# Autopilot.net
KiCad netlist of a schematic drawn in EAGLE
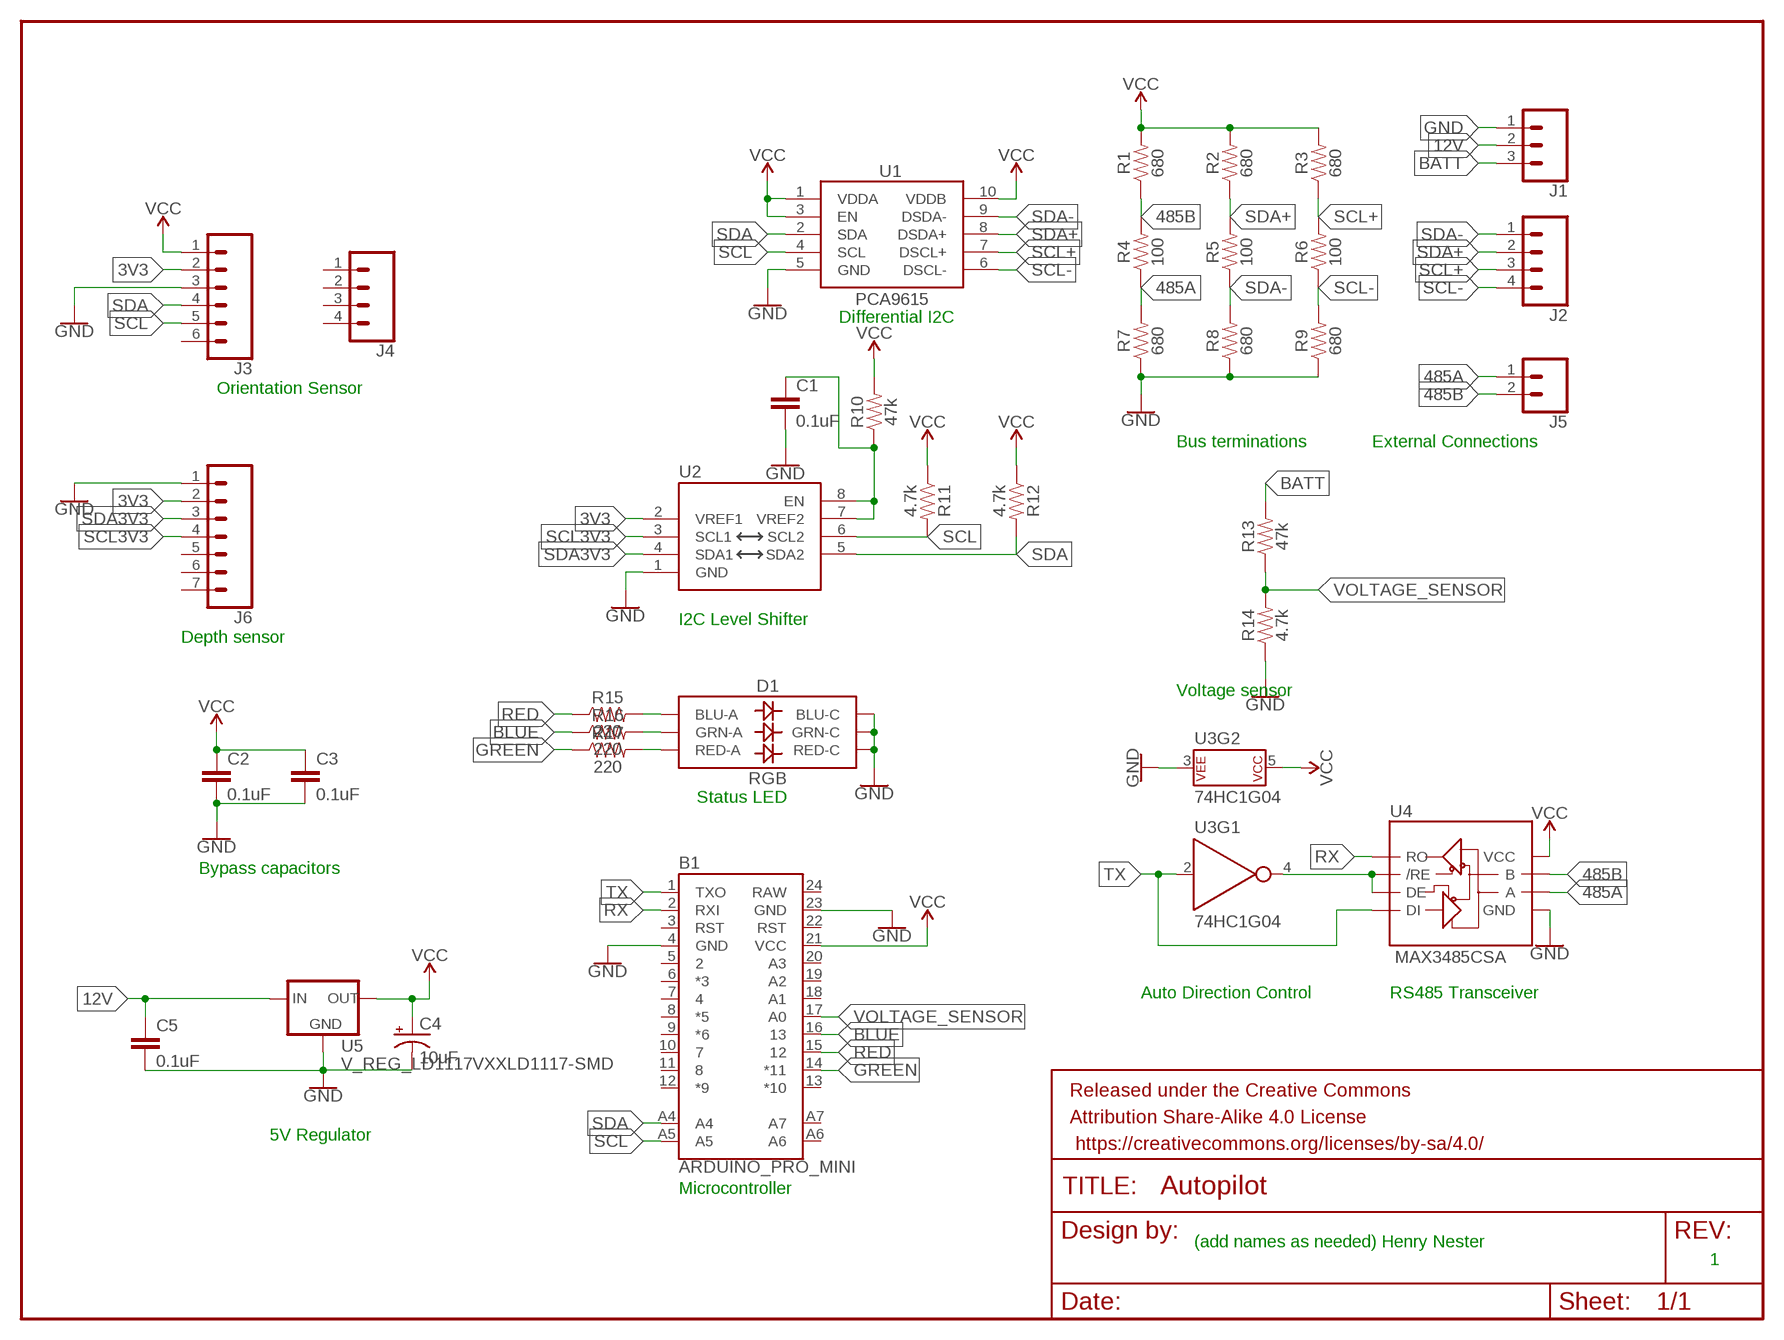
[diagram p0: schematic, sheet 1]

(export (version "E")
  (design (tool "Eeschema 10.0.6"))
  (components
    (comp (ref "B1")
      (value "ARDUINO_PRO_MINI")
      (footprint "eagle-import:ARDUINO_PRO_MINI")
      (libsource (lib "eagle-import") (part "ARDUINO_PRO_MINI"))
    )
    (comp (ref "C1")
      (value "0.1uF")
      (footprint "eagle-import:0603")
      (libsource (lib "eagle-import") (part "0.1UF-0603-25V-(+80/-20%)"))
    )
    (comp (ref "C2")
      (value "0.1uF")
      (footprint "eagle-import:0603")
      (libsource (lib "eagle-import") (part "0.1UF-0603-25V-(+80/-20%)"))
    )
    (comp (ref "C3")
      (value "0.1uF")
      (footprint "eagle-import:0603")
      (libsource (lib "eagle-import") (part "0.1UF-0603-25V-(+80/-20%)"))
    )
    (comp (ref "C4")
      (value "10uF")
      (footprint "eagle-import:CPOL-RADIAL-2.5MM-5MM")
      (libsource (lib "eagle-import") (part "10UF-POLAR-RADIAL-2.5MM-25V-20%"))
    )
    (comp (ref "C5")
      (value "0.1uF")
      (footprint "eagle-import:0603")
      (libsource (lib "eagle-import") (part "0.1UF-0603-25V-(+80/-20%)"))
    )
    (comp (ref "D1")
      (value "RGB")
      (footprint "eagle-import:PLCC-6-LED")
      (libsource (lib "eagle-import") (part "LED-RGBPLCC-6"))
    )
    (comp (ref "FRAME1")
      (value "FRAME-LETTERNO_PACKAGE")
      (footprint "eagle-import:DUMMY")
      (fields (field (name "DESIGNER") "Nobody"))
      (libsource (lib "eagle-import") (part "FRAME-LETTERNO_PACKAGE"))
    )
    (comp (ref "J1")
      (value "CONN_03LONGPADS")
      (footprint "eagle-import:1X03_LONGPADS")
      (libsource (lib "eagle-import") (part "CONN_03LONGPADS"))
    )
    (comp (ref "J2")
      (value "CONN_04")
      (footprint "eagle-import:1X04")
      (libsource (lib "eagle-import") (part "CONN_04"))
    )
    (comp (ref "J3")
      (value "CONN_06NO_SILK_FEMALE_PTH")
      (footprint "eagle-import:1X06_NO_SILK")
      (libsource (lib "eagle-import") (part "CONN_06NO_SILK_FEMALE_PTH"))
    )
    (comp (ref "J4")
      (value "CONN_041X04_NO_SILK")
      (footprint "eagle-import:1X04_NO_SILK")
      (libsource (lib "eagle-import") (part "CONN_041X04_NO_SILK"))
    )
    (comp (ref "J5")
      (value "CONN_02")
      (footprint "eagle-import:1X02")
      (libsource (lib "eagle-import") (part "CONN_02"))
    )
    (comp (ref "J6")
      (value "CONN_07NO_SILK")
      (footprint "eagle-import:1X07_NO_SILK")
      (libsource (lib "eagle-import") (part "CONN_07NO_SILK"))
    )
    (comp (ref "R1")
      (value "680")
      (footprint "eagle-import:0603")
      (libsource (lib "eagle-import") (part "680OHM-0603-1/10W-5%"))
    )
    (comp (ref "R2")
      (value "680")
      (footprint "eagle-import:0603")
      (libsource (lib "eagle-import") (part "680OHM-0603-1/10W-5%"))
    )
    (comp (ref "R3")
      (value "680")
      (footprint "eagle-import:0603")
      (libsource (lib "eagle-import") (part "680OHM-0603-1/10W-5%"))
    )
    (comp (ref "R4")
      (value "100")
      (footprint "eagle-import:0603")
      (libsource (lib "eagle-import") (part "100OHM-0603-1/4W-5%"))
    )
    (comp (ref "R5")
      (value "100")
      (footprint "eagle-import:0603")
      (libsource (lib "eagle-import") (part "100OHM-0603-1/4W-5%"))
    )
    (comp (ref "R6")
      (value "100")
      (footprint "eagle-import:0603")
      (libsource (lib "eagle-import") (part "100OHM-0603-1/4W-5%"))
    )
    (comp (ref "R7")
      (value "680")
      (footprint "eagle-import:0603")
      (libsource (lib "eagle-import") (part "680OHM-0603-1/10W-5%"))
    )
    (comp (ref "R8")
      (value "680")
      (footprint "eagle-import:0603")
      (libsource (lib "eagle-import") (part "680OHM-0603-1/10W-5%"))
    )
    (comp (ref "R9")
      (value "680")
      (footprint "eagle-import:0603")
      (libsource (lib "eagle-import") (part "680OHM-0603-1/10W-5%"))
    )
    (comp (ref "R10")
      (value "47k")
      (footprint "eagle-import:0603")
      (libsource (lib "eagle-import") (part "100KOHM-0603-1/10W-1%"))
    )
    (comp (ref "R11")
      (value "4.7k")
      (footprint "eagle-import:0603")
      (libsource (lib "eagle-import") (part "4.7KOHM-0603-1/10W-1%"))
    )
    (comp (ref "R12")
      (value "4.7k")
      (footprint "eagle-import:0603")
      (libsource (lib "eagle-import") (part "4.7KOHM-0603-1/10W-1%"))
    )
    (comp (ref "R13")
      (value "47k")
      (footprint "eagle-import:0603")
      (libsource (lib "eagle-import") (part "100KOHM-0603-1/10W-1%"))
    )
    (comp (ref "R14")
      (value "4.7k")
      (footprint "eagle-import:0603")
      (libsource (lib "eagle-import") (part "4.7KOHM-0603-1/10W-1%"))
    )
    (comp (ref "R15")
      (value "220")
      (footprint "eagle-import:0603")
      (libsource (lib "eagle-import") (part "220OHM-0603-1/10W-1%"))
    )
    (comp (ref "R16")
      (value "220")
      (footprint "eagle-import:0603")
      (libsource (lib "eagle-import") (part "220OHM-0603-1/10W-1%"))
    )
    (comp (ref "R17")
      (value "220")
      (footprint "eagle-import:0603")
      (libsource (lib "eagle-import") (part "220OHM-0603-1/10W-1%"))
    )
    (comp (ref "U1")
      (value "PCA9615")
      (footprint "eagle-import:TSSOP10")
      (libsource (lib "eagle-import") (part "PCA9615"))
    )
    (comp (ref "U2")
      (value "PCA9306MSOP-8")
      (footprint "eagle-import:MSOP8")
      (libsource (lib "eagle-import") (part "PCA9306MSOP-8"))
    )
    (comp (ref "U3")
      (value "74HC1G04")
      (footprint "eagle-import:SOT353")
      (libsource (lib "eagle-import") (part "741G04HC"))
    )
    (comp (ref "U4")
      (value "MAX3485CSA")
      (footprint "eagle-import:SO08")
      (libsource (lib "eagle-import") (part "RS485SOIC"))
    )
    (comp (ref "U5")
      (value "V_REG_LD1117VXXLD1117-SMD")
      (footprint "eagle-import:SOT223")
      (libsource (lib "eagle-import") (part "V_REG_LD1117VXXLD1117-SMD"))
    )
  )
  (nets
    (net (code "1") (name "/RAW") (class "Default")
      (node (ref "B1") (pin "24") (pinfunction "RAW_24") (pintype "power_in"))
    )
    (net (code "2") (name "3V3") (class "Default")
      (node (ref "J3") (pin "2") (pinfunction "2_2") (pintype "passive"))
      (node (ref "J6") (pin "2") (pinfunction "2_2") (pintype "passive"))
      (node (ref "U2") (pin "2") (pinfunction "VREF1_2") (pintype "bidirectional"))
    )
    (net (code "3") (name "12V") (class "Default")
      (node (ref "C5") (pin "1") (pinfunction "1_1") (pintype "passive"))
      (node (ref "J1") (pin "2") (pinfunction "2_2") (pintype "passive"))
      (node (ref "U5") (pin "3") (pinfunction "IN_3") (pintype "input"))
    )
    (net (code "4") (name "485A") (class "Default")
      (node (ref "J5") (pin "1") (pinfunction "1_1") (pintype "passive"))
      (node (ref "R4") (pin "1") (pinfunction "1_1") (pintype "passive"))
      (node (ref "R7") (pin "2") (pinfunction "2_2") (pintype "passive"))
      (node (ref "U4") (pin "6") (pinfunction "A_6") (pintype "bidirectional"))
    )
    (net (code "5") (name "485B") (class "Default")
      (node (ref "J5") (pin "2") (pinfunction "2_2") (pintype "passive"))
      (node (ref "R1") (pin "1") (pinfunction "1_1") (pintype "passive"))
      (node (ref "R4") (pin "2") (pinfunction "2_2") (pintype "passive"))
      (node (ref "U4") (pin "7") (pinfunction "B_7") (pintype "bidirectional"))
    )
    (net (code "6") (name "BATT") (class "Default")
      (node (ref "J1") (pin "3") (pinfunction "3_3") (pintype "passive"))
      (node (ref "R13") (pin "2") (pinfunction "2_2") (pintype "passive"))
    )
    (net (code "7") (name "BLUE") (class "Default")
      (node (ref "B1") (pin "16") (pinfunction "13_16") (pintype "bidirectional"))
      (node (ref "R16") (pin "1") (pinfunction "1_1") (pintype "passive"))
    )
    (net (code "8") (name "GND") (class "Default")
      (node (ref "B1") (pin "23") (pinfunction "GND_23") (pintype "power_in"))
      (node (ref "B1") (pin "4") (pinfunction "GND_4") (pintype "power_in"))
      (node (ref "C1") (pin "2") (pinfunction "2_2") (pintype "passive"))
      (node (ref "C2") (pin "2") (pinfunction "2_2") (pintype "passive"))
      (node (ref "C3") (pin "2") (pinfunction "2_2") (pintype "passive"))
      (node (ref "C4") (pin "2") (pinfunction "-_2") (pintype "passive"))
      (node (ref "C5") (pin "2") (pinfunction "2_2") (pintype "passive"))
      (node (ref "D1") (pin "CB") (pinfunction "BLU-C_CB") (pintype "bidirectional"))
      (node (ref "D1") (pin "CG") (pinfunction "GRN-C_CG") (pintype "bidirectional"))
      (node (ref "D1") (pin "CR") (pinfunction "RED-C_CR") (pintype "bidirectional"))
      (node (ref "J1") (pin "1") (pinfunction "1_1") (pintype "passive"))
      (node (ref "J3") (pin "3") (pinfunction "3_3") (pintype "passive"))
      (node (ref "J6") (pin "1") (pinfunction "1_1") (pintype "passive"))
      (node (ref "R14") (pin "1") (pinfunction "1_1") (pintype "passive"))
      (node (ref "R7") (pin "1") (pinfunction "1_1") (pintype "passive"))
      (node (ref "R8") (pin "1") (pinfunction "1_1") (pintype "passive"))
      (node (ref "R9") (pin "1") (pinfunction "1_1") (pintype "passive"))
      (node (ref "U1") (pin "5") (pinfunction "GND_5") (pintype "bidirectional"))
      (node (ref "U2") (pin "1") (pinfunction "GND_1") (pintype "bidirectional"))
      (node (ref "U3") (pin "3") (pinfunction "P$V-_3") (pintype "bidirectional"))
      (node (ref "U4") (pin "5") (pinfunction "GND_5") (pintype "bidirectional"))
      (node (ref "U5") (pin "1") (pinfunction "GND_1") (pintype "input"))
    )
    (net (code "9") (name "GREEN") (class "Default")
      (node (ref "B1") (pin "14") (pinfunction "*11_14") (pintype "bidirectional"))
      (node (ref "R17") (pin "1") (pinfunction "1_1") (pintype "passive"))
    )
    (net (code "10") (name "Net-(D1-BLU-A)") (class "Default")
      (node (ref "D1") (pin "AB") (pinfunction "BLU-A_AB") (pintype "bidirectional"))
      (node (ref "R15") (pin "2") (pinfunction "2_2") (pintype "passive"))
    )
    (net (code "11") (name "Net-(D1-GRN-A)") (class "Default")
      (node (ref "D1") (pin "AG") (pinfunction "GRN-A_AG") (pintype "bidirectional"))
      (node (ref "R16") (pin "2") (pinfunction "2_2") (pintype "passive"))
    )
    (net (code "12") (name "Net-(D1-RED-A)") (class "Default")
      (node (ref "D1") (pin "AR") (pinfunction "RED-A_AR") (pintype "bidirectional"))
      (node (ref "R17") (pin "2") (pinfunction "2_2") (pintype "passive"))
    )
    (net (code "13") (name "Net-(U2-EN)") (class "Default")
      (node (ref "C1") (pin "1") (pinfunction "1_1") (pintype "passive"))
      (node (ref "R10") (pin "1") (pinfunction "1_1") (pintype "passive"))
      (node (ref "U2") (pin "7") (pinfunction "VREF2_7") (pintype "bidirectional"))
      (node (ref "U2") (pin "8") (pinfunction "EN_8") (pintype "bidirectional"))
    )
    (net (code "14") (name "Net-(U3A-Y)") (class "Default")
      (node (ref "U3") (pin "4") (pinfunction "Y_4") (pintype "bidirectional"))
      (node (ref "U4") (pin "2") (pinfunction "/RE_2") (pintype "bidirectional"))
      (node (ref "U4") (pin "3") (pinfunction "DE_3") (pintype "bidirectional"))
    )
    (net (code "15") (name "RED") (class "Default")
      (node (ref "B1") (pin "15") (pinfunction "12_15") (pintype "bidirectional"))
      (node (ref "R15") (pin "1") (pinfunction "1_1") (pintype "passive"))
    )
    (net (code "16") (name "RX") (class "Default")
      (node (ref "B1") (pin "2") (pinfunction "RXI_2") (pintype "bidirectional"))
      (node (ref "U4") (pin "1") (pinfunction "RO_1") (pintype "bidirectional"))
    )
    (net (code "17") (name "SCL") (class "Default")
      (node (ref "B1") (pin "A5") (pinfunction "A5_A5") (pintype "bidirectional"))
      (node (ref "J3") (pin "5") (pinfunction "5_5") (pintype "passive"))
      (node (ref "R11") (pin "2") (pinfunction "2_2") (pintype "passive"))
      (node (ref "U1") (pin "4") (pinfunction "SCL_4") (pintype "bidirectional"))
      (node (ref "U2") (pin "6") (pinfunction "SCL2_6") (pintype "bidirectional"))
    )
    (net (code "18") (name "SCL+") (class "Default")
      (node (ref "J2") (pin "3") (pinfunction "3_3") (pintype "passive"))
      (node (ref "R3") (pin "1") (pinfunction "1_1") (pintype "passive"))
      (node (ref "R6") (pin "2") (pinfunction "2_2") (pintype "passive"))
      (node (ref "U1") (pin "7") (pinfunction "DSCL+_7") (pintype "bidirectional"))
    )
    (net (code "19") (name "SCL-") (class "Default")
      (node (ref "J2") (pin "4") (pinfunction "4_4") (pintype "passive"))
      (node (ref "R6") (pin "1") (pinfunction "1_1") (pintype "passive"))
      (node (ref "R9") (pin "2") (pinfunction "2_2") (pintype "passive"))
      (node (ref "U1") (pin "6") (pinfunction "DSCL-_6") (pintype "bidirectional"))
    )
    (net (code "20") (name "SCL3V3") (class "Default")
      (node (ref "J6") (pin "4") (pinfunction "4_4") (pintype "passive"))
      (node (ref "U2") (pin "3") (pinfunction "SCL1_3") (pintype "bidirectional"))
    )
    (net (code "21") (name "SDA") (class "Default")
      (node (ref "B1") (pin "A4") (pinfunction "A4_A4") (pintype "bidirectional"))
      (node (ref "J3") (pin "4") (pinfunction "4_4") (pintype "passive"))
      (node (ref "R12") (pin "2") (pinfunction "2_2") (pintype "passive"))
      (node (ref "U1") (pin "2") (pinfunction "SDA_2") (pintype "bidirectional"))
      (node (ref "U2") (pin "5") (pinfunction "SDA2_5") (pintype "bidirectional"))
    )
    (net (code "22") (name "SDA+") (class "Default")
      (node (ref "J2") (pin "2") (pinfunction "2_2") (pintype "passive"))
      (node (ref "R2") (pin "1") (pinfunction "1_1") (pintype "passive"))
      (node (ref "R5") (pin "2") (pinfunction "2_2") (pintype "passive"))
      (node (ref "U1") (pin "8") (pinfunction "DSDA+_8") (pintype "bidirectional"))
    )
    (net (code "23") (name "SDA-") (class "Default")
      (node (ref "J2") (pin "1") (pinfunction "1_1") (pintype "passive"))
      (node (ref "R5") (pin "1") (pinfunction "1_1") (pintype "passive"))
      (node (ref "R8") (pin "2") (pinfunction "2_2") (pintype "passive"))
      (node (ref "U1") (pin "9") (pinfunction "DSDA-_9") (pintype "bidirectional"))
    )
    (net (code "24") (name "SDA3V3") (class "Default")
      (node (ref "J6") (pin "3") (pinfunction "3_3") (pintype "passive"))
      (node (ref "U2") (pin "4") (pinfunction "SDA1_4") (pintype "bidirectional"))
    )
    (net (code "25") (name "TX") (class "Default")
      (node (ref "B1") (pin "1") (pinfunction "TXO_1") (pintype "bidirectional"))
      (node (ref "U3") (pin "2") (pinfunction "A_2") (pintype "bidirectional"))
      (node (ref "U4") (pin "4") (pinfunction "DI_4") (pintype "bidirectional"))
    )
    (net (code "26") (name "VCC") (class "Default")
      (node (ref "B1") (pin "21") (pinfunction "VCC_21") (pintype "power_in"))
      (node (ref "C2") (pin "1") (pinfunction "1_1") (pintype "passive"))
      (node (ref "C3") (pin "1") (pinfunction "1_1") (pintype "passive"))
      (node (ref "C4") (pin "1") (pinfunction "+_1") (pintype "passive"))
      (node (ref "J3") (pin "1") (pinfunction "1_1") (pintype "passive"))
      (node (ref "R1") (pin "2") (pinfunction "2_2") (pintype "passive"))
      (node (ref "R10") (pin "2") (pinfunction "2_2") (pintype "passive"))
      (node (ref "R11") (pin "1") (pinfunction "1_1") (pintype "passive"))
      (node (ref "R12") (pin "1") (pinfunction "1_1") (pintype "passive"))
      (node (ref "R2") (pin "2") (pinfunction "2_2") (pintype "passive"))
      (node (ref "R3") (pin "2") (pinfunction "2_2") (pintype "passive"))
      (node (ref "U1") (pin "1") (pinfunction "VDDA_1") (pintype "bidirectional"))
      (node (ref "U1") (pin "10") (pinfunction "VDDB_10") (pintype "bidirectional"))
      (node (ref "U1") (pin "3") (pinfunction "EN_3") (pintype "bidirectional"))
      (node (ref "U3") (pin "5") (pinfunction "P$V+_5") (pintype "bidirectional"))
      (node (ref "U4") (pin "8") (pinfunction "VCC_8") (pintype "bidirectional"))
      (node (ref "U5") (pin "2") (pinfunction "OUT_2") (pintype "passive"))
    )
    (net (code "27") (name "VOLTAGE_SENSOR") (class "Default")
      (node (ref "B1") (pin "17") (pinfunction "A0_17") (pintype "bidirectional"))
      (node (ref "R13") (pin "1") (pinfunction "1_1") (pintype "passive"))
      (node (ref "R14") (pin "2") (pinfunction "2_2") (pintype "passive"))
    )
    (net (code "28") (name "unconnected-(B1-*3-Pad6)") (class "Default")
      (node (ref "B1") (pin "6") (pinfunction "*3_6") (pintype "bidirectional"))
    )
    (net (code "29") (name "unconnected-(B1-*5-Pad8)") (class "Default")
      (node (ref "B1") (pin "8") (pinfunction "*5_8") (pintype "bidirectional"))
    )
    (net (code "30") (name "unconnected-(B1-*6-Pad9)") (class "Default")
      (node (ref "B1") (pin "9") (pinfunction "*6_9") (pintype "bidirectional"))
    )
    (net (code "31") (name "unconnected-(B1-*9-Pad12)") (class "Default")
      (node (ref "B1") (pin "12") (pinfunction "*9_12") (pintype "bidirectional"))
    )
    (net (code "32") (name "unconnected-(B1-*10-Pad13)") (class "Default")
      (node (ref "B1") (pin "13") (pinfunction "*10_13") (pintype "bidirectional"))
    )
    (net (code "33") (name "unconnected-(B1-2-Pad5)") (class "Default")
      (node (ref "B1") (pin "5") (pinfunction "2_5") (pintype "bidirectional"))
    )
    (net (code "34") (name "unconnected-(B1-4-Pad7)") (class "Default")
      (node (ref "B1") (pin "7") (pinfunction "4_7") (pintype "bidirectional"))
    )
    (net (code "35") (name "unconnected-(B1-7-Pad10)") (class "Default")
      (node (ref "B1") (pin "10") (pinfunction "7_10") (pintype "bidirectional"))
    )
    (net (code "36") (name "unconnected-(B1-8-Pad11)") (class "Default")
      (node (ref "B1") (pin "11") (pinfunction "8_11") (pintype "bidirectional"))
    )
    (net (code "37") (name "unconnected-(B1-A1-Pad18)") (class "Default")
      (node (ref "B1") (pin "18") (pinfunction "A1_18") (pintype "bidirectional"))
    )
    (net (code "38") (name "unconnected-(B1-A2-Pad19)") (class "Default")
      (node (ref "B1") (pin "19") (pinfunction "A2_19") (pintype "bidirectional"))
    )
    (net (code "39") (name "unconnected-(B1-A3-Pad20)") (class "Default")
      (node (ref "B1") (pin "20") (pinfunction "A3_20") (pintype "bidirectional"))
    )
    (net (code "40") (name "unconnected-(B1-PadA6)") (class "Default")
      (node (ref "B1") (pin "A6") (pinfunction "A6_A6") (pintype "bidirectional"))
    )
    (net (code "41") (name "unconnected-(B1-PadA7)") (class "Default")
      (node (ref "B1") (pin "A7") (pinfunction "A7_A7") (pintype "bidirectional"))
    )
    (net (code "42") (name "unconnected-(B1-RST-Pad3)") (class "Default")
      (node (ref "B1") (pin "3") (pinfunction "RST_3") (pintype "bidirectional"))
    )
    (net (code "43") (name "unconnected-(B1-RST-Pad22)") (class "Default")
      (node (ref "B1") (pin "22") (pinfunction "RST_22") (pintype "bidirectional"))
    )
    (net (code "44") (name "unconnected-(J3-Pad6)") (class "Default")
      (node (ref "J3") (pin "6") (pinfunction "6_6") (pintype "passive"))
    )
    (net (code "45") (name "unconnected-(J4-Pad1)") (class "Default")
      (node (ref "J4") (pin "1") (pinfunction "1_1") (pintype "passive"))
    )
    (net (code "46") (name "unconnected-(J4-Pad2)") (class "Default")
      (node (ref "J4") (pin "2") (pinfunction "2_2") (pintype "passive"))
    )
    (net (code "47") (name "unconnected-(J4-Pad3)") (class "Default")
      (node (ref "J4") (pin "3") (pinfunction "3_3") (pintype "passive"))
    )
    (net (code "48") (name "unconnected-(J4-Pad4)") (class "Default")
      (node (ref "J4") (pin "4") (pinfunction "4_4") (pintype "passive"))
    )
    (net (code "49") (name "unconnected-(J6-Pad5)") (class "Default")
      (node (ref "J6") (pin "5") (pinfunction "5_5") (pintype "passive"))
    )
    (net (code "50") (name "unconnected-(J6-Pad6)") (class "Default")
      (node (ref "J6") (pin "6") (pinfunction "6_6") (pintype "passive"))
    )
    (net (code "51") (name "unconnected-(J6-Pad7)") (class "Default")
      (node (ref "J6") (pin "7") (pinfunction "7_7") (pintype "passive"))
    )
  )
)
